# status_leds.net
KiCad netlist of a schematic drawn in Altium Designer
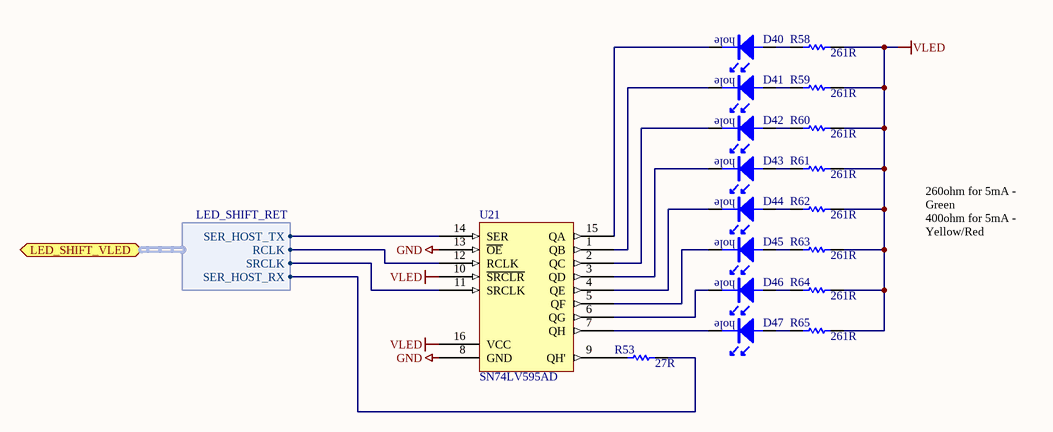
[diagram p0: status_leds.SchDoc]

(export (version "E")
  (design (tool "Eeschema 10.0.6"))
  (components
    (comp (ref "D40")
      (value "~")
      (footprint "LED0.1")
      (description "through hole LED")
      (fields
        (field (name "MANUFACTURER") "TT Electronics/Optek Technology")
        (field (name "MANUFACTURER PART NUMBER") "OVLBG4C7")
      )
      (libsource (lib "RCLDQ") (part "LED_HOLE"))
    )
    (comp (ref "D41")
      (value "~")
      (footprint "LED0.1")
      (description "through hole LED")
      (fields
        (field (name "MANUFACTURER") "TT Electronics/Optek Technology")
        (field (name "MANUFACTURER PART NUMBER") "OVLBG4C7")
      )
      (libsource (lib "RCLDQ") (part "LED_HOLE"))
    )
    (comp (ref "D42")
      (value "~")
      (footprint "LED0.1")
      (description "through hole LED")
      (fields
        (field (name "MANUFACTURER") "TT Electronics/Optek Technology")
        (field (name "MANUFACTURER PART NUMBER") "OVLBG4C7")
      )
      (libsource (lib "RCLDQ") (part "LED_HOLE"))
    )
    (comp (ref "D43")
      (value "~")
      (footprint "LED0.1")
      (description "through hole LED")
      (fields
        (field (name "MANUFACTURER") "TT Electronics/Optek Technology")
        (field (name "MANUFACTURER PART NUMBER") "OVLBG4C7")
      )
      (libsource (lib "RCLDQ") (part "LED_HOLE"))
    )
    (comp (ref "D44")
      (value "~")
      (footprint "LED0.1")
      (description "through hole LED")
      (fields
        (field (name "MANUFACTURER") "TT Electronics/Optek Technology")
        (field (name "MANUFACTURER PART NUMBER") "OVLBG4C7")
      )
      (libsource (lib "RCLDQ") (part "LED_HOLE"))
    )
    (comp (ref "D45")
      (value "~")
      (footprint "LED0.1")
      (description "through hole LED")
      (fields
        (field (name "MANUFACTURER") "TT Electronics/Optek Technology")
        (field (name "MANUFACTURER PART NUMBER") "OVLBG4C7")
      )
      (libsource (lib "RCLDQ") (part "LED_HOLE"))
    )
    (comp (ref "D46")
      (value "~")
      (footprint "LED0.1")
      (description "through hole LED")
      (fields
        (field (name "MANUFACTURER") "TT Electronics/Optek Technology")
        (field (name "MANUFACTURER PART NUMBER") "OVLBG4C7")
      )
      (libsource (lib "RCLDQ") (part "LED_HOLE"))
    )
    (comp (ref "D47")
      (value "~")
      (footprint "LED0.1")
      (description "through hole LED")
      (fields
        (field (name "MANUFACTURER") "TT Electronics/Optek Technology")
        (field (name "MANUFACTURER PART NUMBER") "OVLBG4C7")
      )
      (libsource (lib "RCLDQ") (part "LED_HOLE"))
    )
    (comp (ref "R53")
      (value "27R")
      (footprint "0603")
      (description "Semiconductor Resistor")
      (fields
        (field (name "MANUFACTURER") "Panasonic Electronic Components")
        (field (name "MANUFACTURER PART NUMBER") "ERJ-3EKF27R0V")
        (field (name "PUBLISHER") "Altium Limited")
      )
      (libsource (lib "Miscellaneous Devices") (part "Res Semi"))
    )
    (comp (ref "R58")
      (value "261R")
      (footprint "0603")
      (description "Semiconductor Resistor")
      (fields
        (field (name "MANUFACTURER") "Panasonic Electronic Components")
        (field (name "MANUFACTURER PART NUMBER") "ERJ-3EKF2610V")
        (field (name "PUBLISHER") "Altium Limited")
      )
      (libsource (lib "Miscellaneous Devices") (part "Res Semi"))
    )
    (comp (ref "R59")
      (value "261R")
      (footprint "0603")
      (description "Semiconductor Resistor")
      (fields
        (field (name "MANUFACTURER") "Panasonic Electronic Components")
        (field (name "MANUFACTURER PART NUMBER") "ERJ-3EKF2610V")
        (field (name "PUBLISHER") "Altium Limited")
      )
      (libsource (lib "Miscellaneous Devices") (part "Res Semi"))
    )
    (comp (ref "R60")
      (value "261R")
      (footprint "0603")
      (description "Semiconductor Resistor")
      (fields
        (field (name "MANUFACTURER") "Panasonic Electronic Components")
        (field (name "MANUFACTURER PART NUMBER") "ERJ-3EKF2610V")
        (field (name "PUBLISHER") "Altium Limited")
      )
      (libsource (lib "Miscellaneous Devices") (part "Res Semi"))
    )
    (comp (ref "R61")
      (value "261R")
      (footprint "0603")
      (description "Semiconductor Resistor")
      (fields
        (field (name "MANUFACTURER") "Panasonic Electronic Components")
        (field (name "MANUFACTURER PART NUMBER") "ERJ-3EKF2610V")
        (field (name "PUBLISHER") "Altium Limited")
      )
      (libsource (lib "Miscellaneous Devices") (part "Res Semi"))
    )
    (comp (ref "R62")
      (value "261R")
      (footprint "0603")
      (description "Semiconductor Resistor")
      (fields
        (field (name "MANUFACTURER") "Panasonic Electronic Components")
        (field (name "MANUFACTURER PART NUMBER") "ERJ-3EKF2610V")
        (field (name "PUBLISHER") "Altium Limited")
      )
      (libsource (lib "Miscellaneous Devices") (part "Res Semi"))
    )
    (comp (ref "R63")
      (value "261R")
      (footprint "0603")
      (description "Semiconductor Resistor")
      (fields
        (field (name "MANUFACTURER") "Panasonic Electronic Components")
        (field (name "MANUFACTURER PART NUMBER") "ERJ-3EKF2610V")
        (field (name "PUBLISHER") "Altium Limited")
      )
      (libsource (lib "Miscellaneous Devices") (part "Res Semi"))
    )
    (comp (ref "R64")
      (value "261R")
      (footprint "0603")
      (description "Semiconductor Resistor")
      (fields
        (field (name "MANUFACTURER") "Panasonic Electronic Components")
        (field (name "MANUFACTURER PART NUMBER") "ERJ-3EKF2610V")
        (field (name "PUBLISHER") "Altium Limited")
      )
      (libsource (lib "Miscellaneous Devices") (part "Res Semi"))
    )
    (comp (ref "R65")
      (value "261R")
      (footprint "0603")
      (description "Semiconductor Resistor")
      (fields
        (field (name "MANUFACTURER") "Panasonic Electronic Components")
        (field (name "MANUFACTURER PART NUMBER") "ERJ-3EKF2610V")
        (field (name "PUBLISHER") "Altium Limited")
      )
      (libsource (lib "Miscellaneous Devices") (part "Res Semi"))
    )
    (comp (ref "U21")
      (value "SN74LV595AD")
      (footprint "SOIC127P600X175-16N")
      (description "8-Bit Shift Registers with 3-State Output Registers")
      (fields
        (field (name "MANUFACTURER") "Texas Instruments")
        (field (name "MANUFACTURER PART NUMBER") "SN74LV595ADR")
      )
      (libsource (lib "steve") (part "SN74LV595AD"))
    )
  )
  (nets
    (net (code "2") (name "/RCLK") (class "Default")
      (node (ref "U21") (pin "12") (pinfunction "RCLK_12") (pintype "input"))
    )
    (net (code "3") (name "/SER_HOST_RX") (class "Default")
      (node (ref "R53") (pin "1") (pinfunction "1_1") (pintype "passive"))
    )
    (net (code "4") (name "/SER_HOST_TX") (class "Default")
      (node (ref "U21") (pin "14") (pinfunction "SER_14") (pintype "input"))
    )
    (net (code "5") (name "/SRCLK") (class "Default")
      (node (ref "U21") (pin "11") (pinfunction "SRCLK_11") (pintype "input"))
    )
    (net (code "7") (name "GND") (class "Default")
      (node (ref "U21") (pin "13") (pinfunction "~{OE}_13") (pintype "input"))
      (node (ref "U21") (pin "8") (pinfunction "GND_8") (pintype "power_in"))
    )
    (net (code "8") (name "Net-(D40-PadA)") (class "Default")
      (node (ref "D40") (pin "A") (pinfunction "A_A") (pintype "passive"))
      (node (ref "R58") (pin "2") (pinfunction "2_2") (pintype "passive"))
    )
    (net (code "9") (name "Net-(D41-PadA)") (class "Default")
      (node (ref "D41") (pin "A") (pinfunction "A_A") (pintype "passive"))
      (node (ref "R59") (pin "2") (pinfunction "2_2") (pintype "passive"))
    )
    (net (code "10") (name "Net-(D42-PadA)") (class "Default")
      (node (ref "D42") (pin "A") (pinfunction "A_A") (pintype "passive"))
      (node (ref "R60") (pin "2") (pinfunction "2_2") (pintype "passive"))
    )
    (net (code "11") (name "Net-(D43-PadA)") (class "Default")
      (node (ref "D43") (pin "A") (pinfunction "A_A") (pintype "passive"))
      (node (ref "R61") (pin "2") (pinfunction "2_2") (pintype "passive"))
    )
    (net (code "12") (name "Net-(D44-PadA)") (class "Default")
      (node (ref "D44") (pin "A") (pinfunction "A_A") (pintype "passive"))
      (node (ref "R62") (pin "2") (pinfunction "2_2") (pintype "passive"))
    )
    (net (code "13") (name "Net-(D45-PadA)") (class "Default")
      (node (ref "D45") (pin "A") (pinfunction "A_A") (pintype "passive"))
      (node (ref "R63") (pin "2") (pinfunction "2_2") (pintype "passive"))
    )
    (net (code "14") (name "Net-(D46-PadA)") (class "Default")
      (node (ref "D46") (pin "A") (pinfunction "A_A") (pintype "passive"))
      (node (ref "R64") (pin "2") (pinfunction "2_2") (pintype "passive"))
    )
    (net (code "15") (name "Net-(D47-PadA)") (class "Default")
      (node (ref "D47") (pin "A") (pinfunction "A_A") (pintype "passive"))
      (node (ref "R65") (pin "2") (pinfunction "2_2") (pintype "passive"))
    )
    (net (code "16") (name "Net-(U21-QA)") (class "Default")
      (node (ref "D40") (pin "K") (pinfunction "K_K") (pintype "passive"))
      (node (ref "U21") (pin "15") (pinfunction "QA_15") (pintype "output"))
    )
    (net (code "17") (name "Net-(U21-QB)") (class "Default")
      (node (ref "D41") (pin "K") (pinfunction "K_K") (pintype "passive"))
      (node (ref "U21") (pin "1") (pinfunction "QB_1") (pintype "output"))
    )
    (net (code "18") (name "Net-(U21-QC)") (class "Default")
      (node (ref "D42") (pin "K") (pinfunction "K_K") (pintype "passive"))
      (node (ref "U21") (pin "2") (pinfunction "QC_2") (pintype "output"))
    )
    (net (code "19") (name "Net-(U21-QD)") (class "Default")
      (node (ref "D43") (pin "K") (pinfunction "K_K") (pintype "passive"))
      (node (ref "U21") (pin "3") (pinfunction "QD_3") (pintype "output"))
    )
    (net (code "20") (name "Net-(U21-QE)") (class "Default")
      (node (ref "D44") (pin "K") (pinfunction "K_K") (pintype "passive"))
      (node (ref "U21") (pin "4") (pinfunction "QE_4") (pintype "output"))
    )
    (net (code "21") (name "Net-(U21-QF)") (class "Default")
      (node (ref "D45") (pin "K") (pinfunction "K_K") (pintype "passive"))
      (node (ref "U21") (pin "5") (pinfunction "QF_5") (pintype "output"))
    )
    (net (code "22") (name "Net-(U21-QG)") (class "Default")
      (node (ref "D46") (pin "K") (pinfunction "K_K") (pintype "passive"))
      (node (ref "U21") (pin "6") (pinfunction "QG_6") (pintype "output"))
    )
    (net (code "23") (name "Net-(U21-QH')") (class "Default")
      (node (ref "R53") (pin "2") (pinfunction "2_2") (pintype "passive"))
      (node (ref "U21") (pin "9") (pinfunction "QH'_9") (pintype "output"))
    )
    (net (code "24") (name "Net-(U21-QH)") (class "Default")
      (node (ref "D47") (pin "K") (pinfunction "K_K") (pintype "passive"))
      (node (ref "U21") (pin "7") (pinfunction "QH_7") (pintype "output"))
    )
    (net (code "25") (name "VLED") (class "Default")
      (node (ref "R58") (pin "1") (pinfunction "1_1") (pintype "passive"))
      (node (ref "R59") (pin "1") (pinfunction "1_1") (pintype "passive"))
      (node (ref "R60") (pin "1") (pinfunction "1_1") (pintype "passive"))
      (node (ref "R61") (pin "1") (pinfunction "1_1") (pintype "passive"))
      (node (ref "R62") (pin "1") (pinfunction "1_1") (pintype "passive"))
      (node (ref "R63") (pin "1") (pinfunction "1_1") (pintype "passive"))
      (node (ref "R64") (pin "1") (pinfunction "1_1") (pintype "passive"))
      (node (ref "R65") (pin "1") (pinfunction "1_1") (pintype "passive"))
      (node (ref "U21") (pin "10") (pinfunction "~{SRCLR}_10") (pintype "input"))
      (node (ref "U21") (pin "16") (pinfunction "VCC_16") (pintype "power_in"))
    )
  )
)
